# 05-USB_ETHERNET.net
KiCad netlist of a schematic drawn in Altium Designer
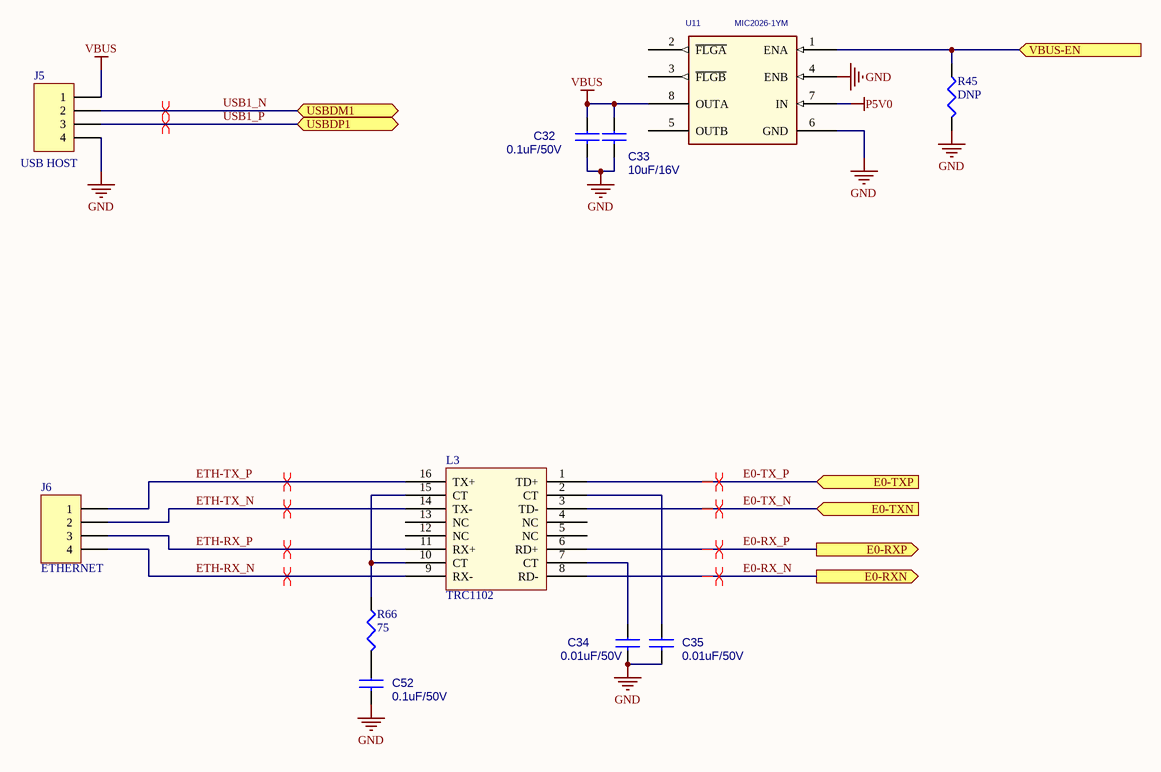
[diagram p0: 05-USB_ETHERNET.SchDoc]

(export (version "E")
  (design (tool "Eeschema 10.0.6"))
  (components
    (comp (ref "C32") (value "0.1uF/50V") (libsource (lib "*") (part "CAP_Dup1")))
    (comp (ref "C33") (value "10uF/16V") (libsource (lib "*") (part "CAP_Dup1")))
    (comp (ref "C34") (value "0.01uF/50V") (libsource (lib "*") (part "CAP_Dup1")))
    (comp (ref "C35") (value "0.01uF/50V") (libsource (lib "*") (part "CAP_Dup1")))
    (comp (ref "C52") (value "0.1uF/50V") (libsource (lib "*") (part "CAP_Dup1")))
    (comp (ref "J5")
      (value "USB HOST")
      (footprint "CONN-2.0-SMD-4P-V")
      (description "Header, 4-Pin")
      (fields (field (name "PUBLISHER") "Altium Limited"))
      (libsource (lib "Miscellaneous Connectors") (part "Header 4"))
    )
    (comp (ref "J6")
      (value "ETHERNET")
      (footprint "CONN-2.0-SMD-4P-V")
      (description "Header, 4-Pin")
      (fields (field (name "PUBLISHER") "Altium Limited"))
      (libsource (lib "Miscellaneous Connectors") (part "Header 4"))
    )
    (comp (ref "L3") (value "TRC1102") (footprint "TRC1102") (libsource (lib "Schlib") (part "TRC1102")))
    (comp (ref "R45") (value "DNP") (footprint "0402") (libsource (lib "*") (part "CR16-1003FM")))
    (comp (ref "R66") (value "75") (footprint "0402") (libsource (lib "*") (part "CR16-1003FM")))
    (comp (ref "U11")
      (value "MIC2026-1YM")
      (footprint "SO8")
      (description "IC LIN SW PWR ACTIVE HIGH DUAL 2.7V-5.5V 0.5A SOIC8")
      (libsource (lib "*") (part "MIC2526_8P"))
    )
  )
  (nets
    (net (code "1") (name "/E0-RX_N") (class "Default")
      (node (ref "L3") (pin "8") (pinfunction "RD-_8") (pintype "passive"))
    )
    (net (code "2") (name "/E0-RX_P") (class "Default")
      (node (ref "L3") (pin "6") (pinfunction "RD+_6") (pintype "passive"))
    )
    (net (code "3") (name "/E0-TX_N") (class "Default")
      (node (ref "L3") (pin "3") (pinfunction "TD-_3") (pintype "passive"))
    )
    (net (code "4") (name "/E0-TX_P") (class "Default")
      (node (ref "L3") (pin "1") (pinfunction "TD+_1") (pintype "passive"))
    )
    (net (code "5") (name "/ETH-RX_N") (class "Default")
      (node (ref "J6") (pin "4") (pinfunction "4_4") (pintype "passive"))
      (node (ref "L3") (pin "9") (pinfunction "RX-_9") (pintype "passive"))
    )
    (net (code "6") (name "/ETH-RX_P") (class "Default")
      (node (ref "J6") (pin "3") (pinfunction "3_3") (pintype "passive"))
      (node (ref "L3") (pin "11") (pinfunction "RX+_11") (pintype "passive"))
    )
    (net (code "7") (name "/ETH-TX_N") (class "Default")
      (node (ref "J6") (pin "2") (pinfunction "2_2") (pintype "passive"))
      (node (ref "L3") (pin "14") (pinfunction "TX-_14") (pintype "passive"))
    )
    (net (code "8") (name "/ETH-TX_P") (class "Default")
      (node (ref "J6") (pin "1") (pinfunction "1_1") (pintype "passive"))
      (node (ref "L3") (pin "16") (pinfunction "TX+_16") (pintype "passive"))
    )
    (net (code "9") (name "/USB1_N") (class "Default")
      (node (ref "J5") (pin "2") (pinfunction "2_2") (pintype "passive"))
    )
    (net (code "10") (name "/USB1_P") (class "Default")
      (node (ref "J5") (pin "3") (pinfunction "3_3") (pintype "passive"))
    )
    (net (code "11") (name "/VBUS-EN") (class "Default")
      (node (ref "R45") (pin "2") (pinfunction "2_2") (pintype "passive"))
      (node (ref "U11") (pin "1") (pinfunction "ENA_1") (pintype "input"))
    )
    (net (code "12") (name "GND") (class "Default")
      (node (ref "C32") (pin "2") (pinfunction "2_2") (pintype "passive"))
      (node (ref "C33") (pin "2") (pinfunction "2_2") (pintype "passive"))
      (node (ref "C34") (pin "2") (pinfunction "2_2") (pintype "passive"))
      (node (ref "C35") (pin "2") (pinfunction "2_2") (pintype "passive"))
      (node (ref "C52") (pin "2") (pinfunction "2_2") (pintype "passive"))
      (node (ref "J5") (pin "4") (pinfunction "4_4") (pintype "passive"))
      (node (ref "R45") (pin "1") (pinfunction "1_1") (pintype "passive"))
      (node (ref "U11") (pin "4") (pinfunction "ENB_4") (pintype "input"))
      (node (ref "U11") (pin "6") (pinfunction "GND_6") (pintype "power_in"))
    )
    (net (code "13") (name "Net-(C34-Pad1)") (class "Default")
      (node (ref "C34") (pin "1") (pinfunction "1_1") (pintype "passive"))
      (node (ref "L3") (pin "7") (pinfunction "CT_7") (pintype "passive"))
    )
    (net (code "14") (name "Net-(C35-Pad1)") (class "Default")
      (node (ref "C35") (pin "1") (pinfunction "1_1") (pintype "passive"))
      (node (ref "L3") (pin "2") (pinfunction "CT_2") (pintype "passive"))
    )
    (net (code "15") (name "Net-(C52-Pad1)") (class "Default")
      (node (ref "C52") (pin "1") (pinfunction "1_1") (pintype "passive"))
      (node (ref "R66") (pin "1") (pinfunction "1_1") (pintype "passive"))
    )
    (net (code "16") (name "Net-(L3-CT-Pad10)") (class "Default")
      (node (ref "L3") (pin "10") (pinfunction "CT_10") (pintype "passive"))
      (node (ref "L3") (pin "15") (pinfunction "CT_15") (pintype "passive"))
      (node (ref "R66") (pin "2") (pinfunction "2_2") (pintype "passive"))
    )
    (net (code "17") (name "P5V0") (class "Default")
      (node (ref "U11") (pin "7") (pinfunction "IN_7") (pintype "input"))
    )
    (net (code "18") (name "VBUS") (class "Default")
      (node (ref "C32") (pin "1") (pinfunction "1_1") (pintype "passive"))
      (node (ref "C33") (pin "1") (pinfunction "1_1") (pintype "passive"))
      (node (ref "J5") (pin "1") (pinfunction "1_1") (pintype "passive"))
      (node (ref "U11") (pin "8") (pinfunction "OUTA_8") (pintype "power_in"))
    )
    (net (code "19") (name "unconnected-(L3-NC-Pad4)") (class "Default")
      (node (ref "L3") (pin "4") (pinfunction "NC_4") (pintype "passive"))
    )
    (net (code "20") (name "unconnected-(L3-NC-Pad5)") (class "Default")
      (node (ref "L3") (pin "5") (pinfunction "NC_5") (pintype "passive"))
    )
    (net (code "21") (name "unconnected-(L3-NC-Pad12)") (class "Default")
      (node (ref "L3") (pin "12") (pinfunction "NC_12") (pintype "passive"))
    )
    (net (code "22") (name "unconnected-(L3-NC-Pad13)") (class "Default")
      (node (ref "L3") (pin "13") (pinfunction "NC_13") (pintype "passive"))
    )
    (net (code "23") (name "unconnected-(U11-OUTB-Pad5)") (class "Default")
      (node (ref "U11") (pin "5") (pinfunction "OUTB_5") (pintype "power_in"))
    )
    (net (code "24") (name "unconnected-(U11-~{FLGA}-Pad2)") (class "Default")
      (node (ref "U11") (pin "2") (pinfunction "~{FLGA}_2") (pintype "output"))
    )
    (net (code "25") (name "unconnected-(U11-~{FLGB}-Pad3)") (class "Default")
      (node (ref "U11") (pin "3") (pinfunction "~{FLGB}_3") (pintype "output"))
    )
  )
)
